# psg-basic.net
KiCad netlist of a schematic drawn in EAGLE
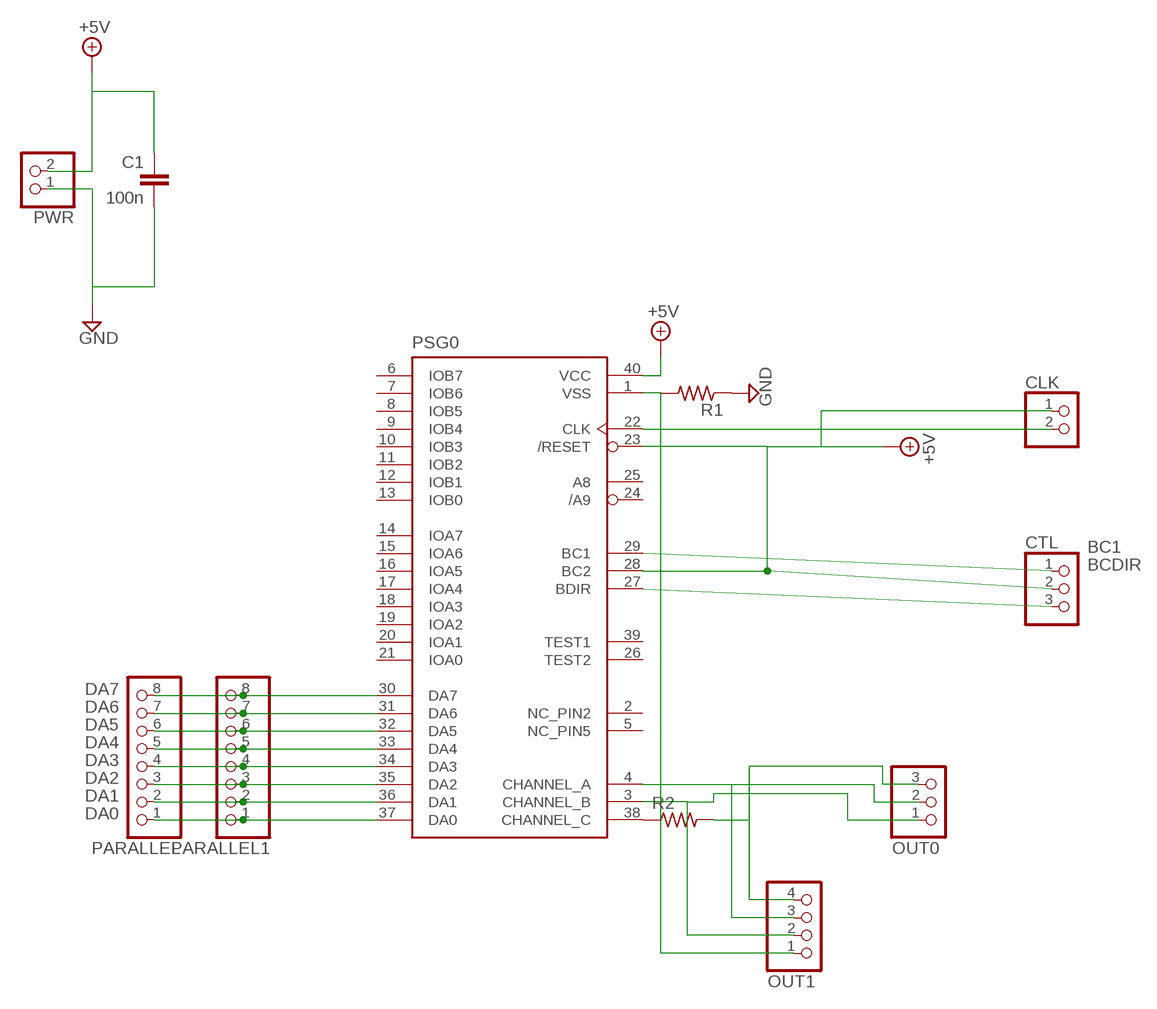
[diagram p0: schematic, sheet 1]

(export (version "E")
  (design (tool "Eeschema 10.0.6"))
  (components
    (comp (ref "C1")
      (value "100n")
      (footprint "eagle-import:050X030_025")
      (libsource (lib "eagle-import") (part "050X030_0251"))
    )
    (comp (ref "CLK")
      (value "PINHD-1X2")
      (footprint "eagle-import:1X02")
      (libsource (lib "eagle-import") (part "PINHD-1X2"))
    )
    (comp (ref "CTL")
      (value "PINHD-1X3")
      (footprint "eagle-import:1X03")
      (libsource (lib "eagle-import") (part "PINHD-1X3"))
    )
    (comp (ref "OUT0")
      (value "PINHD-1X3")
      (footprint "eagle-import:1X03")
      (libsource (lib "eagle-import") (part "PINHD-1X3"))
    )
    (comp (ref "OUT1")
      (value "PINHD-1X4/90")
      (footprint "eagle-import:1X04_90")
      (libsource (lib "eagle-import") (part "PINHD-1X4/90"))
    )
    (comp (ref "PARALLEL")
      (value "PINHD-1X8")
      (footprint "eagle-import:1X08")
      (libsource (lib "eagle-import") (part "PINHD-1X8"))
    )
    (comp (ref "PARALLEL1")
      (value "PINHD-1X8")
      (footprint "eagle-import:1X08")
      (libsource (lib "eagle-import") (part "PINHD-1X8"))
    )
    (comp (ref "PSG0")
      (value "AY-3-8910")
      (footprint "eagle-import:DIL40")
      (libsource (lib "eagle-import") (part "AY-3-8910"))
    )
    (comp (ref "PWR")
      (value "PINHD-1X2")
      (footprint "eagle-import:1X02")
      (libsource (lib "eagle-import") (part "PINHD-1X2"))
    )
    (comp (ref "R1")
      (value "6MM.4.1")
      (footprint "eagle-import:R0207_4A")
      (libsource (lib "eagle-import") (part "6MM.4.1"))
    )
    (comp (ref "R2")
      (value "6MM.5")
      (footprint "eagle-import:R0207_5")
      (libsource (lib "eagle-import") (part "6MM.5"))
    )
  )
  (nets
    (net (code "1") (name "+5V") (class "Default")
      (node (ref "C1") (pin "1") (pinfunction "1_1") (pintype "passive"))
      (node (ref "CLK") (pin "1") (pinfunction "1_1") (pintype "passive"))
      (node (ref "CTL") (pin "2") (pinfunction "2_2") (pintype "passive"))
      (node (ref "PSG0") (pin "23") (pinfunction "/RESET_23") (pintype "input"))
      (node (ref "PSG0") (pin "28") (pinfunction "BC2_28") (pintype "input"))
      (node (ref "PSG0") (pin "40") (pinfunction "VCC_40") (pintype "power_in"))
      (node (ref "PWR") (pin "2") (pinfunction "2_2") (pintype "passive"))
    )
    (net (code "2") (name "/BC1") (class "Default")
      (node (ref "CTL") (pin "1") (pinfunction "1_1") (pintype "passive"))
      (node (ref "PSG0") (pin "29") (pinfunction "BC1_29") (pintype "input"))
    )
    (net (code "3") (name "/BCDIR") (class "Default")
      (node (ref "CTL") (pin "3") (pinfunction "3_3") (pintype "passive"))
      (node (ref "PSG0") (pin "27") (pinfunction "BDIR_27") (pintype "input"))
    )
    (net (code "4") (name "/DA0") (class "Default")
      (node (ref "PARALLEL") (pin "1") (pinfunction "1_1") (pintype "passive"))
      (node (ref "PARALLEL1") (pin "1") (pinfunction "1_1") (pintype "passive"))
      (node (ref "PSG0") (pin "37") (pinfunction "DA0_37") (pintype "bidirectional"))
    )
    (net (code "5") (name "/DA1") (class "Default")
      (node (ref "PARALLEL") (pin "2") (pinfunction "2_2") (pintype "passive"))
      (node (ref "PARALLEL1") (pin "2") (pinfunction "2_2") (pintype "passive"))
      (node (ref "PSG0") (pin "36") (pinfunction "DA1_36") (pintype "bidirectional"))
    )
    (net (code "6") (name "/DA2") (class "Default")
      (node (ref "PARALLEL") (pin "3") (pinfunction "3_3") (pintype "passive"))
      (node (ref "PARALLEL1") (pin "3") (pinfunction "3_3") (pintype "passive"))
      (node (ref "PSG0") (pin "35") (pinfunction "DA2_35") (pintype "bidirectional"))
    )
    (net (code "7") (name "/DA3") (class "Default")
      (node (ref "PARALLEL") (pin "4") (pinfunction "4_4") (pintype "passive"))
      (node (ref "PARALLEL1") (pin "4") (pinfunction "4_4") (pintype "passive"))
      (node (ref "PSG0") (pin "34") (pinfunction "DA3_34") (pintype "bidirectional"))
    )
    (net (code "8") (name "/DA4") (class "Default")
      (node (ref "PARALLEL") (pin "5") (pinfunction "5_5") (pintype "passive"))
      (node (ref "PARALLEL1") (pin "5") (pinfunction "5_5") (pintype "passive"))
      (node (ref "PSG0") (pin "33") (pinfunction "DA4_33") (pintype "bidirectional"))
    )
    (net (code "9") (name "/DA5") (class "Default")
      (node (ref "PARALLEL") (pin "6") (pinfunction "6_6") (pintype "passive"))
      (node (ref "PARALLEL1") (pin "6") (pinfunction "6_6") (pintype "passive"))
      (node (ref "PSG0") (pin "32") (pinfunction "DA5_32") (pintype "bidirectional"))
    )
    (net (code "10") (name "/DA6") (class "Default")
      (node (ref "PARALLEL") (pin "7") (pinfunction "7_7") (pintype "passive"))
      (node (ref "PARALLEL1") (pin "7") (pinfunction "7_7") (pintype "passive"))
      (node (ref "PSG0") (pin "31") (pinfunction "DA6_31") (pintype "bidirectional"))
    )
    (net (code "11") (name "/DA7") (class "Default")
      (node (ref "PARALLEL") (pin "8") (pinfunction "8_8") (pintype "passive"))
      (node (ref "PARALLEL1") (pin "8") (pinfunction "8_8") (pintype "passive"))
      (node (ref "PSG0") (pin "30") (pinfunction "DA7_30") (pintype "bidirectional"))
    )
    (net (code "12") (name "GND") (class "Default")
      (node (ref "C1") (pin "2") (pinfunction "2_2") (pintype "passive"))
      (node (ref "PWR") (pin "1") (pinfunction "1_1") (pintype "passive"))
      (node (ref "R1") (pin "1") (pinfunction "1_1") (pintype "passive"))
    )
    (net (code "13") (name "Net-(OUT0-Pad3)") (class "Default")
      (node (ref "OUT0") (pin "3") (pinfunction "3_3") (pintype "passive"))
      (node (ref "OUT1") (pin "4") (pinfunction "4_4") (pintype "passive"))
      (node (ref "R2") (pin "2") (pinfunction "2_2") (pintype "passive"))
    )
    (net (code "14") (name "Net-(PSG0-CHANNEL_A)") (class "Default")
      (node (ref "OUT0") (pin "2") (pinfunction "2_2") (pintype "passive"))
      (node (ref "OUT1") (pin "3") (pinfunction "3_3") (pintype "passive"))
      (node (ref "PSG0") (pin "4") (pinfunction "CHANNEL_A_4") (pintype "output"))
    )
    (net (code "15") (name "Net-(PSG0-CHANNEL_B)") (class "Default")
      (node (ref "OUT0") (pin "1") (pinfunction "1_1") (pintype "passive"))
      (node (ref "OUT1") (pin "2") (pinfunction "2_2") (pintype "passive"))
      (node (ref "PSG0") (pin "3") (pinfunction "CHANNEL_B_3") (pintype "output"))
    )
    (net (code "16") (name "Net-(PSG0-CHANNEL_C)") (class "Default")
      (node (ref "PSG0") (pin "38") (pinfunction "CHANNEL_C_38") (pintype "output"))
      (node (ref "R2") (pin "1") (pinfunction "1_1") (pintype "passive"))
    )
    (net (code "17") (name "Net-(PSG0-CLK)") (class "Default")
      (node (ref "CLK") (pin "2") (pinfunction "2_2") (pintype "passive"))
      (node (ref "PSG0") (pin "22") (pinfunction "CLK_22") (pintype "input"))
    )
    (net (code "18") (name "Net-(PSG0-VSS)") (class "Default")
      (node (ref "OUT1") (pin "1") (pinfunction "1_1") (pintype "passive"))
      (node (ref "PSG0") (pin "1") (pinfunction "VSS_1") (pintype "power_in"))
      (node (ref "R1") (pin "2") (pinfunction "2_2") (pintype "passive"))
    )
    (net (code "19") (name "unconnected-(PSG0-A8-Pad25)") (class "Default")
      (node (ref "PSG0") (pin "25") (pinfunction "A8_25") (pintype "bidirectional"))
    )
    (net (code "20") (name "unconnected-(PSG0-IOA0-Pad21)") (class "Default")
      (node (ref "PSG0") (pin "21") (pinfunction "IOA0_21") (pintype "bidirectional"))
    )
    (net (code "21") (name "unconnected-(PSG0-IOA1-Pad20)") (class "Default")
      (node (ref "PSG0") (pin "20") (pinfunction "IOA1_20") (pintype "bidirectional"))
    )
    (net (code "22") (name "unconnected-(PSG0-IOA2-Pad19)") (class "Default")
      (node (ref "PSG0") (pin "19") (pinfunction "IOA2_19") (pintype "bidirectional"))
    )
    (net (code "23") (name "unconnected-(PSG0-IOA3-Pad18)") (class "Default")
      (node (ref "PSG0") (pin "18") (pinfunction "IOA3_18") (pintype "bidirectional"))
    )
    (net (code "24") (name "unconnected-(PSG0-IOA4-Pad17)") (class "Default")
      (node (ref "PSG0") (pin "17") (pinfunction "IOA4_17") (pintype "bidirectional"))
    )
    (net (code "25") (name "unconnected-(PSG0-IOA5-Pad16)") (class "Default")
      (node (ref "PSG0") (pin "16") (pinfunction "IOA5_16") (pintype "bidirectional"))
    )
    (net (code "26") (name "unconnected-(PSG0-IOA6-Pad15)") (class "Default")
      (node (ref "PSG0") (pin "15") (pinfunction "IOA6_15") (pintype "bidirectional"))
    )
    (net (code "27") (name "unconnected-(PSG0-IOA7-Pad14)") (class "Default")
      (node (ref "PSG0") (pin "14") (pinfunction "IOA7_14") (pintype "bidirectional"))
    )
    (net (code "28") (name "unconnected-(PSG0-IOB0-Pad13)") (class "Default")
      (node (ref "PSG0") (pin "13") (pinfunction "IOB0_13") (pintype "bidirectional"))
    )
    (net (code "29") (name "unconnected-(PSG0-IOB1-Pad12)") (class "Default")
      (node (ref "PSG0") (pin "12") (pinfunction "IOB1_12") (pintype "bidirectional"))
    )
    (net (code "30") (name "unconnected-(PSG0-IOB2-Pad11)") (class "Default")
      (node (ref "PSG0") (pin "11") (pinfunction "IOB2_11") (pintype "bidirectional"))
    )
    (net (code "31") (name "unconnected-(PSG0-IOB3-Pad10)") (class "Default")
      (node (ref "PSG0") (pin "10") (pinfunction "IOB3_10") (pintype "bidirectional"))
    )
    (net (code "32") (name "unconnected-(PSG0-IOB4-Pad9)") (class "Default")
      (node (ref "PSG0") (pin "9") (pinfunction "IOB4_9") (pintype "bidirectional"))
    )
    (net (code "33") (name "unconnected-(PSG0-IOB5-Pad8)") (class "Default")
      (node (ref "PSG0") (pin "8") (pinfunction "IOB5_8") (pintype "bidirectional"))
    )
    (net (code "34") (name "unconnected-(PSG0-IOB6-Pad7)") (class "Default")
      (node (ref "PSG0") (pin "7") (pinfunction "IOB6_7") (pintype "bidirectional"))
    )
    (net (code "35") (name "unconnected-(PSG0-IOB7-Pad6)") (class "Default")
      (node (ref "PSG0") (pin "6") (pinfunction "IOB7_6") (pintype "bidirectional"))
    )
    (net (code "36") (name "unconnected-(PSG0-NC_PIN2-Pad2)") (class "Default")
      (node (ref "PSG0") (pin "2") (pinfunction "NC_PIN2_2") (pintype "no_connect"))
    )
    (net (code "37") (name "unconnected-(PSG0-NC_PIN5-Pad5)") (class "Default")
      (node (ref "PSG0") (pin "5") (pinfunction "NC_PIN5_5") (pintype "bidirectional"))
    )
    (net (code "38") (name "unconnected-(PSG0-TEST1-Pad39)") (class "Default")
      (node (ref "PSG0") (pin "39") (pinfunction "TEST1_39") (pintype "no_connect"))
    )
    (net (code "39") (name "unconnected-(PSG0-TEST2-Pad26)") (class "Default")
      (node (ref "PSG0") (pin "26") (pinfunction "TEST2_26") (pintype "no_connect"))
    )
    (net (code "40") (name "unconnected-(PSG0-{slash}A9-Pad24)") (class "Default")
      (node (ref "PSG0") (pin "24") (pinfunction "/A9_24") (pintype "bidirectional"))
    )
  )
)
